# piezo.net
KiCad netlist of a schematic drawn in EAGLE
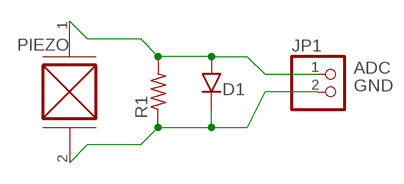
[diagram p0: schematic, sheet 1]

(export (version "E")
  (design (tool "Eeschema 10.0.6"))
  (components
    (comp (ref "D1")
      (value "1N4148-3")
      (footprint "eagle-import:DO35-3")
      (libsource (lib "eagle-import") (part "1N4148-3"))
    )
    (comp (ref "JP1")
      (value "HEADER-1X2")
      (footprint "eagle-import:1X02_OVAL")
      (libsource (lib "eagle-import") (part "HEADER-1X2"))
    )
    (comp (ref "R1")
      (value "R-US_0204/7")
      (footprint "eagle-import:0204_7")
      (libsource (lib "eagle-import") (part "R-US_0204/7"))
    )
    (comp (ref "U$1")
      (value "PIEZO")
      (footprint "eagle-import:1X02_PEIZO")
      (libsource (lib "eagle-import") (part "PIEZO"))
    )
  )
  (nets
    (net (code "1") (name "/ADC") (class "Default")
      (node (ref "D1") (pin "A") (pinfunction "A_A") (pintype "passive"))
      (node (ref "JP1") (pin "1") (pinfunction "1_1") (pintype "passive"))
      (node (ref "R1") (pin "2") (pinfunction "2_2") (pintype "passive"))
      (node (ref "U$1") (pin "1") (pinfunction "GND_1") (pintype "passive"))
    )
    (net (code "2") (name "/GND") (class "Default")
      (node (ref "D1") (pin "C") (pinfunction "C_C") (pintype "passive"))
      (node (ref "JP1") (pin "2") (pinfunction "2_2") (pintype "passive"))
      (node (ref "R1") (pin "1") (pinfunction "1_1") (pintype "passive"))
      (node (ref "U$1") (pin "2") (pinfunction "OUT+_2") (pintype "passive"))
    )
  )
)
